# switchy_stamp_pth_mk2_inverting.net
KiCad netlist of a schematic drawn in EAGLE
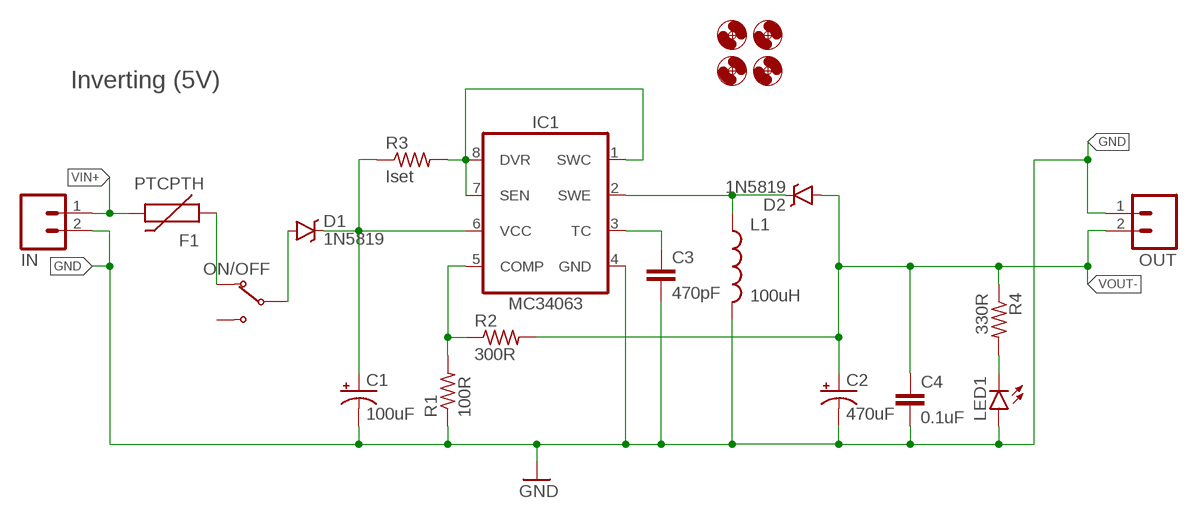
[diagram p0: schematic, sheet 1]

(export (version "E")
  (design (tool "Eeschema 10.0.6"))
  (components
    (comp (ref "C1")
      (value "100uF")
      (footprint "eagle-import:E2,5-7")
      (libsource (lib "eagle-import") (part "CAPACITOR-POLARIZEDE2.5-7"))
    )
    (comp (ref "C2")
      (value "470uF")
      (footprint "eagle-import:E2,5-7")
      (libsource (lib "eagle-import") (part "CAPACITOR-POLARIZEDE2.5-7"))
    )
    (comp (ref "C3")
      (value "470pF")
      (footprint "eagle-import:C025-024X044")
      (libsource (lib "eagle-import") (part "CAPACITOR-CERAMIC025-024X044"))
    )
    (comp (ref "C4")
      (value "0.1uF")
      (footprint "eagle-import:C025-024X044")
      (libsource (lib "eagle-import") (part "CAPACITOR-CERAMIC025-024X044"))
    )
    (comp (ref "D1")
      (value "1N5819")
      (footprint "eagle-import:DO-41")
      (libsource (lib "eagle-import") (part "DIODE-SCHOTTKYDO-41"))
    )
    (comp (ref "D2")
      (value "1N5819")
      (footprint "eagle-import:DO-41")
      (libsource (lib "eagle-import") (part "DIODE-SCHOTTKYDO-41"))
    )
    (comp (ref "F1")
      (value "PTCPTH")
      (footprint "eagle-import:PTC")
      (libsource (lib "eagle-import") (part "PTCPTH"))
    )
    (comp (ref "H1")
      (value "HOLE#2")
      (footprint "eagle-import:HOLE-#2")
      (libsource (lib "eagle-import") (part "HOLE#2"))
    )
    (comp (ref "H2")
      (value "HOLE#2")
      (footprint "eagle-import:HOLE-#2")
      (libsource (lib "eagle-import") (part "HOLE#2"))
    )
    (comp (ref "H3")
      (value "HOLE#2")
      (footprint "eagle-import:HOLE-#2")
      (libsource (lib "eagle-import") (part "HOLE#2"))
    )
    (comp (ref "H4")
      (value "HOLE#2")
      (footprint "eagle-import:HOLE-#2")
      (libsource (lib "eagle-import") (part "HOLE#2"))
    )
    (comp (ref "IC1")
      (value "MC34063")
      (footprint "eagle-import:DIP-08")
      (libsource (lib "eagle-import") (part "MC34063DIP"))
    )
    (comp (ref "IN")
      (value "M02JST-PTH-2")
      (footprint "eagle-import:JST-2-PH-RA-PTH")
      (libsource (lib "eagle-import") (part "M02JST-PTH-2"))
    )
    (comp (ref "L1")
      (value "100uH")
      (footprint "eagle-import:RADIAL-PTH-3-BY-6.7DIA")
      (libsource (lib "eagle-import") (part "INDUCTORRADIAL-PTH-3-BY-6.7DIA"))
    )
    (comp (ref "LED1")
      (value "LED3MM")
      (footprint "eagle-import:LED3MM")
      (libsource (lib "eagle-import") (part "LED3MM"))
    )
    (comp (ref "ON/OFF")
      (value "SWITCH-SPDTPTH-RA-2.54MM")
      (footprint "eagle-import:SPDT-RA-2.54MM")
      (libsource (lib "eagle-import") (part "SWITCH-SPDTPTH-RA-2.54MM"))
    )
    (comp (ref "OUT")
      (value "M02JST-PTH-2")
      (footprint "eagle-import:JST-2-PH-RA-PTH")
      (libsource (lib "eagle-import") (part "M02JST-PTH-2"))
    )
    (comp (ref "R1")
      (value "100R")
      (footprint "eagle-import:RESISTOR-AXIAL-PTH-7.68MM")
      (libsource (lib "eagle-import") (part "RESISTORPTH-AXIAL-7.68MM"))
    )
    (comp (ref "R2")
      (value "300R")
      (footprint "eagle-import:RESISTOR-AXIAL-PTH-7.68MM")
      (libsource (lib "eagle-import") (part "RESISTORPTH-AXIAL-7.68MM"))
    )
    (comp (ref "R3")
      (value "Iset")
      (footprint "eagle-import:RESISTOR-AXIAL-PTH-7.68MM")
      (libsource (lib "eagle-import") (part "RESISTORPTH-AXIAL-7.68MM"))
    )
    (comp (ref "R4")
      (value "330R")
      (footprint "eagle-import:RESISTOR-AXIAL-PTH-7.68MM")
      (libsource (lib "eagle-import") (part "RESISTORPTH-AXIAL-7.68MM"))
    )
  )
  (nets
    (net (code "1") (name "GND") (class "Default")
      (node (ref "C1") (pin "-") (pinfunction "-_-") (pintype "passive"))
      (node (ref "C2") (pin "-") (pinfunction "-_-") (pintype "passive"))
      (node (ref "C3") (pin "2") (pinfunction "2_2") (pintype "passive"))
      (node (ref "C4") (pin "2") (pinfunction "2_2") (pintype "passive"))
      (node (ref "IC1") (pin "4") (pinfunction "GND_4") (pintype "bidirectional"))
      (node (ref "IN") (pin "2") (pinfunction "2_2") (pintype "passive"))
      (node (ref "L1") (pin "P$2") (pinfunction "2_P$2") (pintype "passive"))
      (node (ref "LED1") (pin "A") (pinfunction "A_A") (pintype "passive"))
      (node (ref "OUT") (pin "1") (pinfunction "1_1") (pintype "passive"))
      (node (ref "R1") (pin "P$1") (pinfunction "1_P$1") (pintype "passive"))
    )
    (net (code "2") (name "Net-(F1-1)") (class "Default")
      (node (ref "F1") (pin "P$1") (pinfunction "1_P$1") (pintype "bidirectional"))
      (node (ref "ON/OFF") (pin "1") (pinfunction "NC_1") (pintype "passive"))
    )
    (net (code "3") (name "Net-(IC1-COMP)") (class "Default")
      (node (ref "IC1") (pin "5") (pinfunction "COMP_5") (pintype "bidirectional"))
      (node (ref "R1") (pin "P$2") (pinfunction "2_P$2") (pintype "passive"))
      (node (ref "R2") (pin "P$1") (pinfunction "1_P$1") (pintype "passive"))
    )
    (net (code "4") (name "Net-(IC1-DVR)") (class "Default")
      (node (ref "IC1") (pin "1") (pinfunction "SWC_1") (pintype "bidirectional"))
      (node (ref "IC1") (pin "7") (pinfunction "SEN_7") (pintype "bidirectional"))
      (node (ref "IC1") (pin "8") (pinfunction "DVR_8") (pintype "bidirectional"))
      (node (ref "R3") (pin "P$2") (pinfunction "2_P$2") (pintype "passive"))
    )
    (net (code "5") (name "Net-(IC1-SWE)") (class "Default")
      (node (ref "D2") (pin "C") (pinfunction "C_C") (pintype "passive"))
      (node (ref "IC1") (pin "2") (pinfunction "SWE_2") (pintype "bidirectional"))
      (node (ref "L1") (pin "P$1") (pinfunction "1_P$1") (pintype "passive"))
    )
    (net (code "6") (name "Net-(IC1-TC)") (class "Default")
      (node (ref "C3") (pin "1") (pinfunction "1_1") (pintype "passive"))
      (node (ref "IC1") (pin "3") (pinfunction "TC_3") (pintype "bidirectional"))
    )
    (net (code "7") (name "Net-(IC1-VCC)") (class "Default")
      (node (ref "C1") (pin "+") (pinfunction "+_+") (pintype "passive"))
      (node (ref "D1") (pin "C") (pinfunction "C_C") (pintype "passive"))
      (node (ref "IC1") (pin "6") (pinfunction "VCC_6") (pintype "bidirectional"))
      (node (ref "R3") (pin "P$1") (pinfunction "1_P$1") (pintype "passive"))
    )
    (net (code "8") (name "Net-(LED1-C)") (class "Default")
      (node (ref "LED1") (pin "K") (pinfunction "C_K") (pintype "passive"))
      (node (ref "R4") (pin "P$2") (pinfunction "2_P$2") (pintype "passive"))
    )
    (net (code "9") (name "Net-(ON/OFF-COM)") (class "Default")
      (node (ref "D1") (pin "A") (pinfunction "A_A") (pintype "passive"))
      (node (ref "ON/OFF") (pin "2") (pinfunction "COM_2") (pintype "passive"))
    )
    (net (code "10") (name "VIN+") (class "Default")
      (node (ref "F1") (pin "P$2") (pinfunction "2_P$2") (pintype "bidirectional"))
      (node (ref "IN") (pin "1") (pinfunction "1_1") (pintype "passive"))
    )
    (net (code "11") (name "VOUT-") (class "Default")
      (node (ref "C2") (pin "+") (pinfunction "+_+") (pintype "passive"))
      (node (ref "C4") (pin "1") (pinfunction "1_1") (pintype "passive"))
      (node (ref "D2") (pin "A") (pinfunction "A_A") (pintype "passive"))
      (node (ref "OUT") (pin "2") (pinfunction "2_2") (pintype "passive"))
      (node (ref "R2") (pin "P$2") (pinfunction "2_P$2") (pintype "passive"))
      (node (ref "R4") (pin "P$1") (pinfunction "1_P$1") (pintype "passive"))
    )
    (net (code "12") (name "unconnected-(ON/OFF-NO-Pad3)") (class "Default")
      (node (ref "ON/OFF") (pin "3") (pinfunction "NO_3") (pintype "passive"))
    )
  )
)
